# IO.net
KiCad netlist of a schematic drawn in Altium Designer
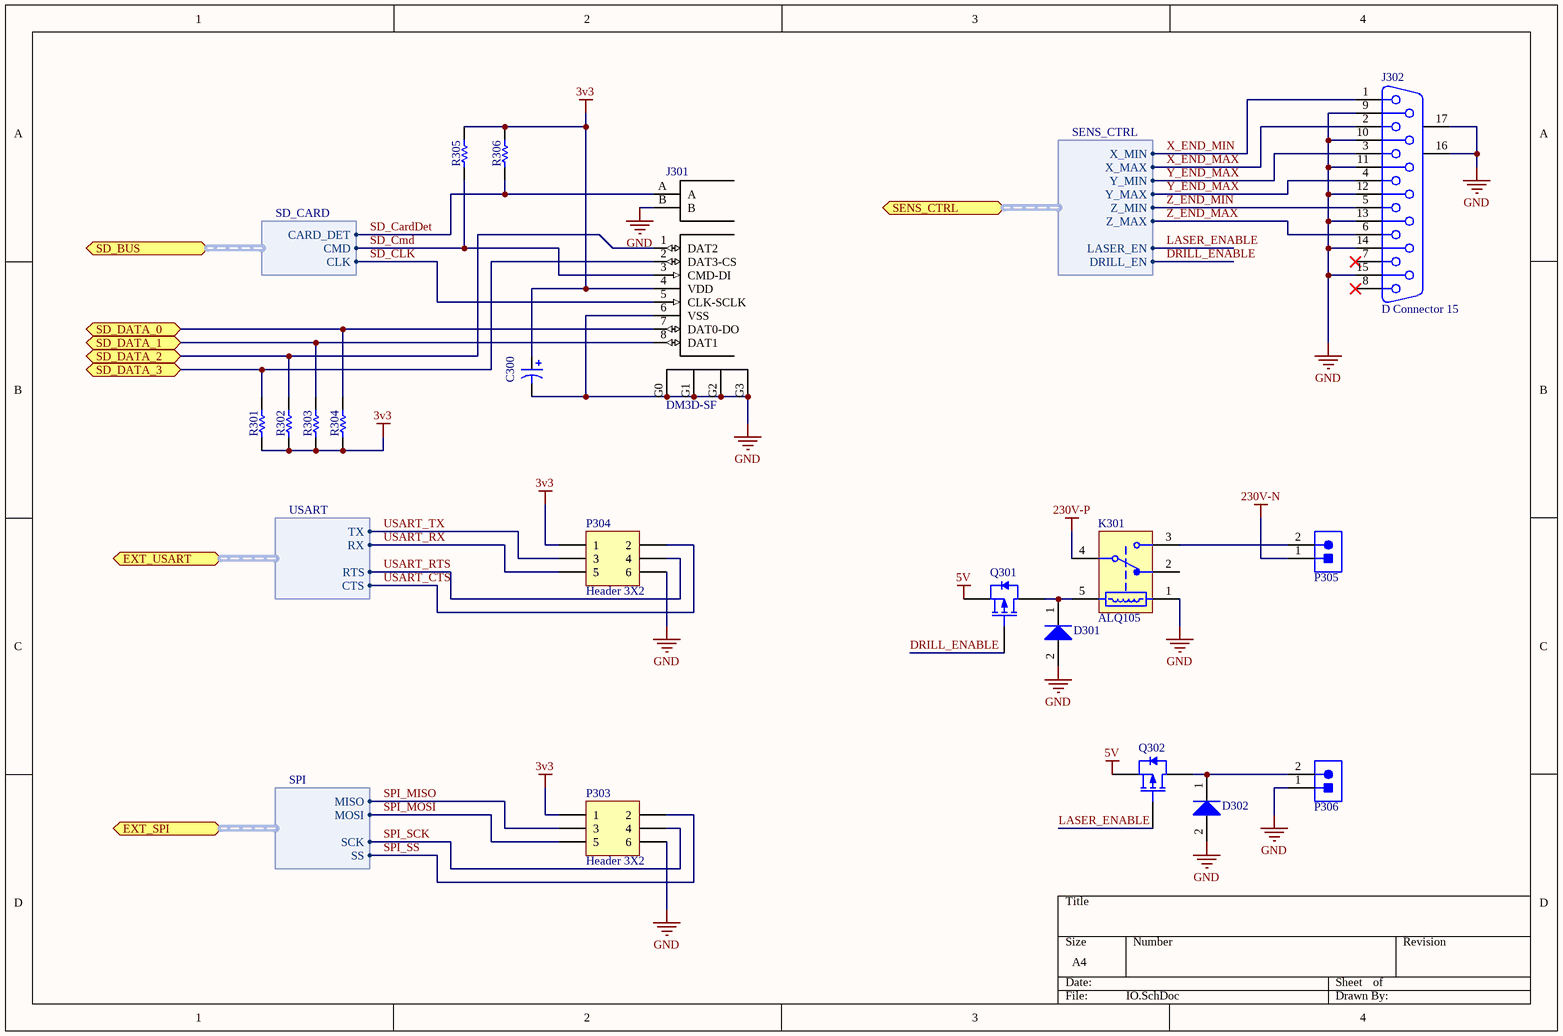
[diagram p0: IO.SchDoc]

(export (version "E")
  (design (tool "Eeschema 10.0.6"))
  (components
    (comp (ref "C300")
      (value "T491B")
      (footprint "B")
      (description "Solid Tantalum Chip Capacitor, Standard T491 Series - Industrial Grade")
      (fields (field (name "PUBLISHER") "Altium Limited"))
      (libsource (lib "KEMET Chip Capacitor") (part "T491B"))
    )
    (comp (ref "D301")
      (value "NSR0340HT1G")
      (footprint "ONSC-SOD-323-2-477-02_V")
      (description "Schottky Barrier Diode, 2-Pin SOD-323, Pb-Free, Tape and Reel")
      (fields (field (name "MANUFACTURER") "On Semiconductor"))
      (libsource (lib "Altium Content Vault") (part "CMP-1055-00472-1"))
    )
    (comp (ref "D302")
      (value "NSR0340HT1G")
      (footprint "ONSC-SOD-323-2-477-02_V")
      (description "Schottky Barrier Diode, 2-Pin SOD-323, Pb-Free, Tape and Reel")
      (fields (field (name "MANUFACTURER") "On Semiconductor"))
      (libsource (lib "Altium Content Vault") (part "CMP-1055-00472-1"))
    )
    (comp (ref "J301") (value "DM3D-SF") (footprint "DM3D-SF") (libsource (lib "INSA") (part "DM3D-SF")))
    (comp (ref "J302")
      (value "D Connector 15")
      (footprint "DSUB1.385-2H15")
      (description "Receptacle Assembly, 15 Position, Right Angle")
      (fields (field (name "PUBLISHER") "Altium Limited"))
      (libsource (lib "Miscellaneous Connectors") (part "D Connector 15"))
    )
    (comp (ref "K301")
      (value "ALQ105")
      (footprint "PNSC-LQ-5-2000x1000x1600_V")
      (fields (field (name "MANUFACTURER") "Panasonic"))
      (libsource (lib "Altium Content Vault") (part "PNSC-ALQ105-LQ-5-2000x1000x1600-5"))
    )
    (comp (ref "P303")
      (value "Header 3X2")
      (footprint "HDR2X3")
      (description "Header, 3-Pin, Dual row")
      (fields (field (name "PUBLISHER") "Altium Limited"))
      (libsource (lib "Miscellaneous Connectors") (part "Header 3X2"))
    )
    (comp (ref "P304")
      (value "Header 3X2")
      (footprint "HDR2X3")
      (description "Header, 3-Pin, Dual row")
      (fields (field (name "PUBLISHER") "Altium Limited"))
      (libsource (lib "Miscellaneous Connectors") (part "Header 3X2"))
    )
    (comp (ref "P305")
      (value "SCREW-5.0/5.08 2WAYS")
      (footprint "SCREW-5.0-2WAYS_V")
      (description "Socket, Screw Terminal Block, 2 Way, 5.0 mm Pitch, 90 Degree Angle, Through-Hole")
      (fields (field (name "MANUFACTURER") "No Vendor"))
      (libsource (lib "Altium Content Vault") (part "CMP-0617-00009-1"))
    )
    (comp (ref "P306")
      (value "SCREW-5.0/5.08 2WAYS")
      (footprint "SCREW-5.0-2WAYS_V")
      (description "Socket, Screw Terminal Block, 2 Way, 5.0 mm Pitch, 90 Degree Angle, Through-Hole")
      (fields (field (name "MANUFACTURER") "No Vendor"))
      (libsource (lib "Altium Content Vault") (part "CMP-0617-00009-1"))
    )
    (comp (ref "Q301")
      (value "BSS84")
      (footprint "SOT23_N")
      (description "P-channel Enhancement Mode Vertical D-MOSFET")
      (fields (field (name "PUBLISHER") "Altium Limited"))
      (libsource (lib "Philips Discrete MOSFET - Low Power") (part "BSS84"))
    )
    (comp (ref "Q302")
      (value "BSS84")
      (footprint "SOT23_N")
      (description "P-channel Enhancement Mode Vertical D-MOSFET")
      (fields (field (name "PUBLISHER") "Altium Limited"))
      (libsource (lib "Philips Discrete MOSFET - Low Power") (part "BSS84"))
    )
    (comp (ref "R301")
      (value "1K 5% 1206(3216)")
      (footprint "RESC1206(3216)_M")
      (description "1K 0.25W 5% 1206 (3216 Metric)  SMD")
      (fields (field (name "TOLERANCE") "5 %") (field (name "POWER") "0.25 W"))
      (libsource (lib "Altium Content Vault") (part "RES"))
    )
    (comp (ref "R302")
      (value "1K 5% 1206(3216)")
      (footprint "RESC1206(3216)_M")
      (description "1K 0.25W 5% 1206 (3216 Metric)  SMD")
      (fields (field (name "TOLERANCE") "5 %") (field (name "POWER") "0.25 W"))
      (libsource (lib "Altium Content Vault") (part "RES"))
    )
    (comp (ref "R303")
      (value "1K 5% 1206(3216)")
      (footprint "RESC1206(3216)_M")
      (description "1K 0.25W 5% 1206 (3216 Metric)  SMD")
      (fields (field (name "TOLERANCE") "5 %") (field (name "POWER") "0.25 W"))
      (libsource (lib "Altium Content Vault") (part "RES"))
    )
    (comp (ref "R304")
      (value "1K 5% 1206(3216)")
      (footprint "RESC1206(3216)_M")
      (description "1K 0.25W 5% 1206 (3216 Metric)  SMD")
      (fields (field (name "TOLERANCE") "5 %") (field (name "POWER") "0.25 W"))
      (libsource (lib "Altium Content Vault") (part "RES"))
    )
    (comp (ref "R305")
      (value "1K 5% 1206(3216)")
      (footprint "RESC1206(3216)_M")
      (description "1K 0.25W 5% 1206 (3216 Metric)  SMD")
      (fields (field (name "TOLERANCE") "5 %") (field (name "POWER") "0.25 W"))
      (libsource (lib "Altium Content Vault") (part "RES"))
    )
    (comp (ref "R306")
      (value "1K 5% 1206(3216)")
      (footprint "RESC1206(3216)_M")
      (description "1K 0.25W 5% 1206 (3216 Metric)  SMD")
      (fields (field (name "TOLERANCE") "5 %") (field (name "POWER") "0.25 W"))
      (libsource (lib "Altium Content Vault") (part "RES"))
    )
  )
  (nets
    (net (code "5") (name "/DRILL_ENABLE") (class "Default")
      (node (ref "Q301") (pin "1") (pinfunction "G_1") (pintype "passive"))
    )
    (net (code "6") (name "/LASER_ENABLE") (class "Default")
      (node (ref "Q302") (pin "1") (pinfunction "G_1") (pintype "passive"))
    )
    (net (code "7") (name "/SD_CLK") (class "Default")
      (node (ref "J301") (pin "5") (pinfunction "CLK-SCLK_5") (pintype "input"))
    )
    (net (code "8") (name "/SD_CardDet") (class "Default")
      (node (ref "J301") (pin "A") (pinfunction "A_A") (pintype "passive"))
      (node (ref "R306") (pin "1") (pinfunction "1_1") (pintype "passive"))
    )
    (net (code "9") (name "/SD_Cmd") (class "Default")
      (node (ref "J301") (pin "3") (pinfunction "CMD-DI_3") (pintype "input"))
      (node (ref "R305") (pin "1") (pinfunction "1_1") (pintype "passive"))
    )
    (net (code "10") (name "/SD_DATA_0") (class "Default")
      (node (ref "J301") (pin "7") (pinfunction "DAT0-DO_7") (pintype "bidirectional"))
      (node (ref "R304") (pin "2") (pinfunction "2_2") (pintype "passive"))
    )
    (net (code "11") (name "/SD_DATA_1") (class "Default")
      (node (ref "J301") (pin "8") (pinfunction "DAT1_8") (pintype "bidirectional"))
      (node (ref "R303") (pin "2") (pinfunction "2_2") (pintype "passive"))
    )
    (net (code "12") (name "/SD_DATA_2") (class "Default")
      (node (ref "J301") (pin "1") (pinfunction "DAT2_1") (pintype "bidirectional"))
      (node (ref "R302") (pin "2") (pinfunction "2_2") (pintype "passive"))
    )
    (net (code "13") (name "/SD_DATA_3") (class "Default")
      (node (ref "J301") (pin "2") (pinfunction "DAT3-CS_2") (pintype "bidirectional"))
      (node (ref "R301") (pin "2") (pinfunction "2_2") (pintype "passive"))
    )
    (net (code "14") (name "/SPI_MISO") (class "Default")
      (node (ref "P303") (pin "3") (pinfunction "3_3") (pintype "passive"))
    )
    (net (code "15") (name "/SPI_MOSI") (class "Default")
      (node (ref "P303") (pin "5") (pinfunction "5_5") (pintype "passive"))
    )
    (net (code "16") (name "/SPI_SCK") (class "Default")
      (node (ref "P303") (pin "4") (pinfunction "4_4") (pintype "passive"))
    )
    (net (code "17") (name "/SPI_SS") (class "Default")
      (node (ref "P303") (pin "2") (pinfunction "2_2") (pintype "passive"))
    )
    (net (code "18") (name "/USART_CTS") (class "Default")
      (node (ref "P304") (pin "2") (pinfunction "2_2") (pintype "passive"))
    )
    (net (code "19") (name "/USART_RTS") (class "Default")
      (node (ref "P304") (pin "4") (pinfunction "4_4") (pintype "passive"))
    )
    (net (code "20") (name "/USART_RX") (class "Default")
      (node (ref "P304") (pin "5") (pinfunction "5_5") (pintype "passive"))
    )
    (net (code "21") (name "/USART_TX") (class "Default")
      (node (ref "P304") (pin "3") (pinfunction "3_3") (pintype "passive"))
    )
    (net (code "22") (name "/X_END_MAX") (class "Default")
      (node (ref "J302") (pin "2") (pinfunction "2_2") (pintype "passive"))
    )
    (net (code "23") (name "/X_END_MIN") (class "Default")
      (node (ref "J302") (pin "1") (pinfunction "1_1") (pintype "passive"))
    )
    (net (code "24") (name "/Y_END_MAX") (class "Default")
      (node (ref "J302") (pin "3") (pinfunction "3_3") (pintype "passive"))
      (node (ref "J302") (pin "4") (pinfunction "4_4") (pintype "passive"))
    )
    (net (code "25") (name "/Z_END_MAX") (class "Default")
      (node (ref "J302") (pin "6") (pinfunction "6_6") (pintype "passive"))
    )
    (net (code "26") (name "/Z_END_MIN") (class "Default")
      (node (ref "J302") (pin "5") (pinfunction "5_5") (pintype "passive"))
    )
    (net (code "31") (name "3v3") (class "Default")
      (node (ref "C300") (pin "1") (pinfunction "1_1") (pintype "passive"))
      (node (ref "J301") (pin "4") (pinfunction "VDD_4") (pintype "power_in"))
      (node (ref "P303") (pin "1") (pinfunction "1_1") (pintype "passive"))
      (node (ref "P304") (pin "1") (pinfunction "1_1") (pintype "passive"))
      (node (ref "R301") (pin "1") (pinfunction "1_1") (pintype "passive"))
      (node (ref "R302") (pin "1") (pinfunction "1_1") (pintype "passive"))
      (node (ref "R303") (pin "1") (pinfunction "1_1") (pintype "passive"))
      (node (ref "R304") (pin "1") (pinfunction "1_1") (pintype "passive"))
      (node (ref "R305") (pin "2") (pinfunction "2_2") (pintype "passive"))
      (node (ref "R306") (pin "2") (pinfunction "2_2") (pintype "passive"))
    )
    (net (code "32") (name "5V") (class "Default")
      (node (ref "Q301") (pin "2") (pinfunction "S_2") (pintype "passive"))
      (node (ref "Q302") (pin "2") (pinfunction "S_2") (pintype "passive"))
    )
    (net (code "33") (name "230V-N") (class "Default")
      (node (ref "P305") (pin "1") (pinfunction "1_1") (pintype "passive"))
    )
    (net (code "34") (name "230V-P") (class "Default")
      (node (ref "K301") (pin "4") (pinfunction "COM_4") (pintype "passive"))
    )
    (net (code "35") (name "GND") (class "Default")
      (node (ref "C300") (pin "2") (pinfunction "2_2") (pintype "passive"))
      (node (ref "D301") (pin "2") (pinfunction "A_2") (pintype "passive"))
      (node (ref "D302") (pin "2") (pinfunction "A_2") (pintype "passive"))
      (node (ref "J301") (pin "6") (pinfunction "VSS_6") (pintype "power_in"))
      (node (ref "J301") (pin "B") (pinfunction "B_B") (pintype "passive"))
      (node (ref "J301") (pin "G0") (pinfunction "9_G0") (pintype "passive"))
      (node (ref "J301") (pin "G1") (pinfunction "10_G1") (pintype "passive"))
      (node (ref "J301") (pin "G2") (pinfunction "11_G2") (pintype "passive"))
      (node (ref "J301") (pin "G3") (pinfunction "12_G3") (pintype "passive"))
      (node (ref "J302") (pin "10") (pinfunction "10_10") (pintype "passive"))
      (node (ref "J302") (pin "11") (pinfunction "11_11") (pintype "passive"))
      (node (ref "J302") (pin "12") (pinfunction "12_12") (pintype "passive"))
      (node (ref "J302") (pin "13") (pinfunction "13_13") (pintype "passive"))
      (node (ref "J302") (pin "14") (pinfunction "14_14") (pintype "passive"))
      (node (ref "J302") (pin "15") (pinfunction "15_15") (pintype "passive"))
      (node (ref "J302") (pin "16") (pinfunction "MH1_16") (pintype "passive"))
      (node (ref "J302") (pin "17") (pinfunction "MH2_17") (pintype "passive"))
      (node (ref "J302") (pin "9") (pinfunction "9_9") (pintype "passive"))
      (node (ref "K301") (pin "1") (pinfunction "1_1") (pintype "passive"))
      (node (ref "P303") (pin "6") (pinfunction "6_6") (pintype "passive"))
      (node (ref "P304") (pin "6") (pinfunction "6_6") (pintype "passive"))
      (node (ref "P306") (pin "1") (pinfunction "1_1") (pintype "passive"))
    )
    (net (code "36") (name "Net-(D301-K)") (class "Default")
      (node (ref "D301") (pin "1") (pinfunction "K_1") (pintype "passive"))
      (node (ref "K301") (pin "5") (pinfunction "5_5") (pintype "passive"))
      (node (ref "Q301") (pin "3") (pinfunction "D_3") (pintype "passive"))
    )
    (net (code "37") (name "Net-(D302-K)") (class "Default")
      (node (ref "D302") (pin "1") (pinfunction "K_1") (pintype "passive"))
      (node (ref "P306") (pin "2") (pinfunction "2_2") (pintype "passive"))
      (node (ref "Q302") (pin "3") (pinfunction "D_3") (pintype "passive"))
    )
    (net (code "38") (name "Net-(K301-NO)") (class "Default")
      (node (ref "K301") (pin "3") (pinfunction "NO_3") (pintype "passive"))
      (node (ref "P305") (pin "2") (pinfunction "2_2") (pintype "passive"))
    )
    (net (code "39") (name "unconnected-(J302-Pad7)") (class "Default")
      (node (ref "J302") (pin "7") (pinfunction "7_7") (pintype "passive+no_connect"))
    )
    (net (code "40") (name "unconnected-(J302-Pad8)") (class "Default")
      (node (ref "J302") (pin "8") (pinfunction "8_8") (pintype "passive+no_connect"))
    )
    (net (code "41") (name "unconnected-(K301-NC-Pad2)") (class "Default")
      (node (ref "K301") (pin "2") (pinfunction "NC_2") (pintype "passive"))
    )
  )
)
